# ad_1.net
KiCad netlist of a schematic drawn in Altium Designer
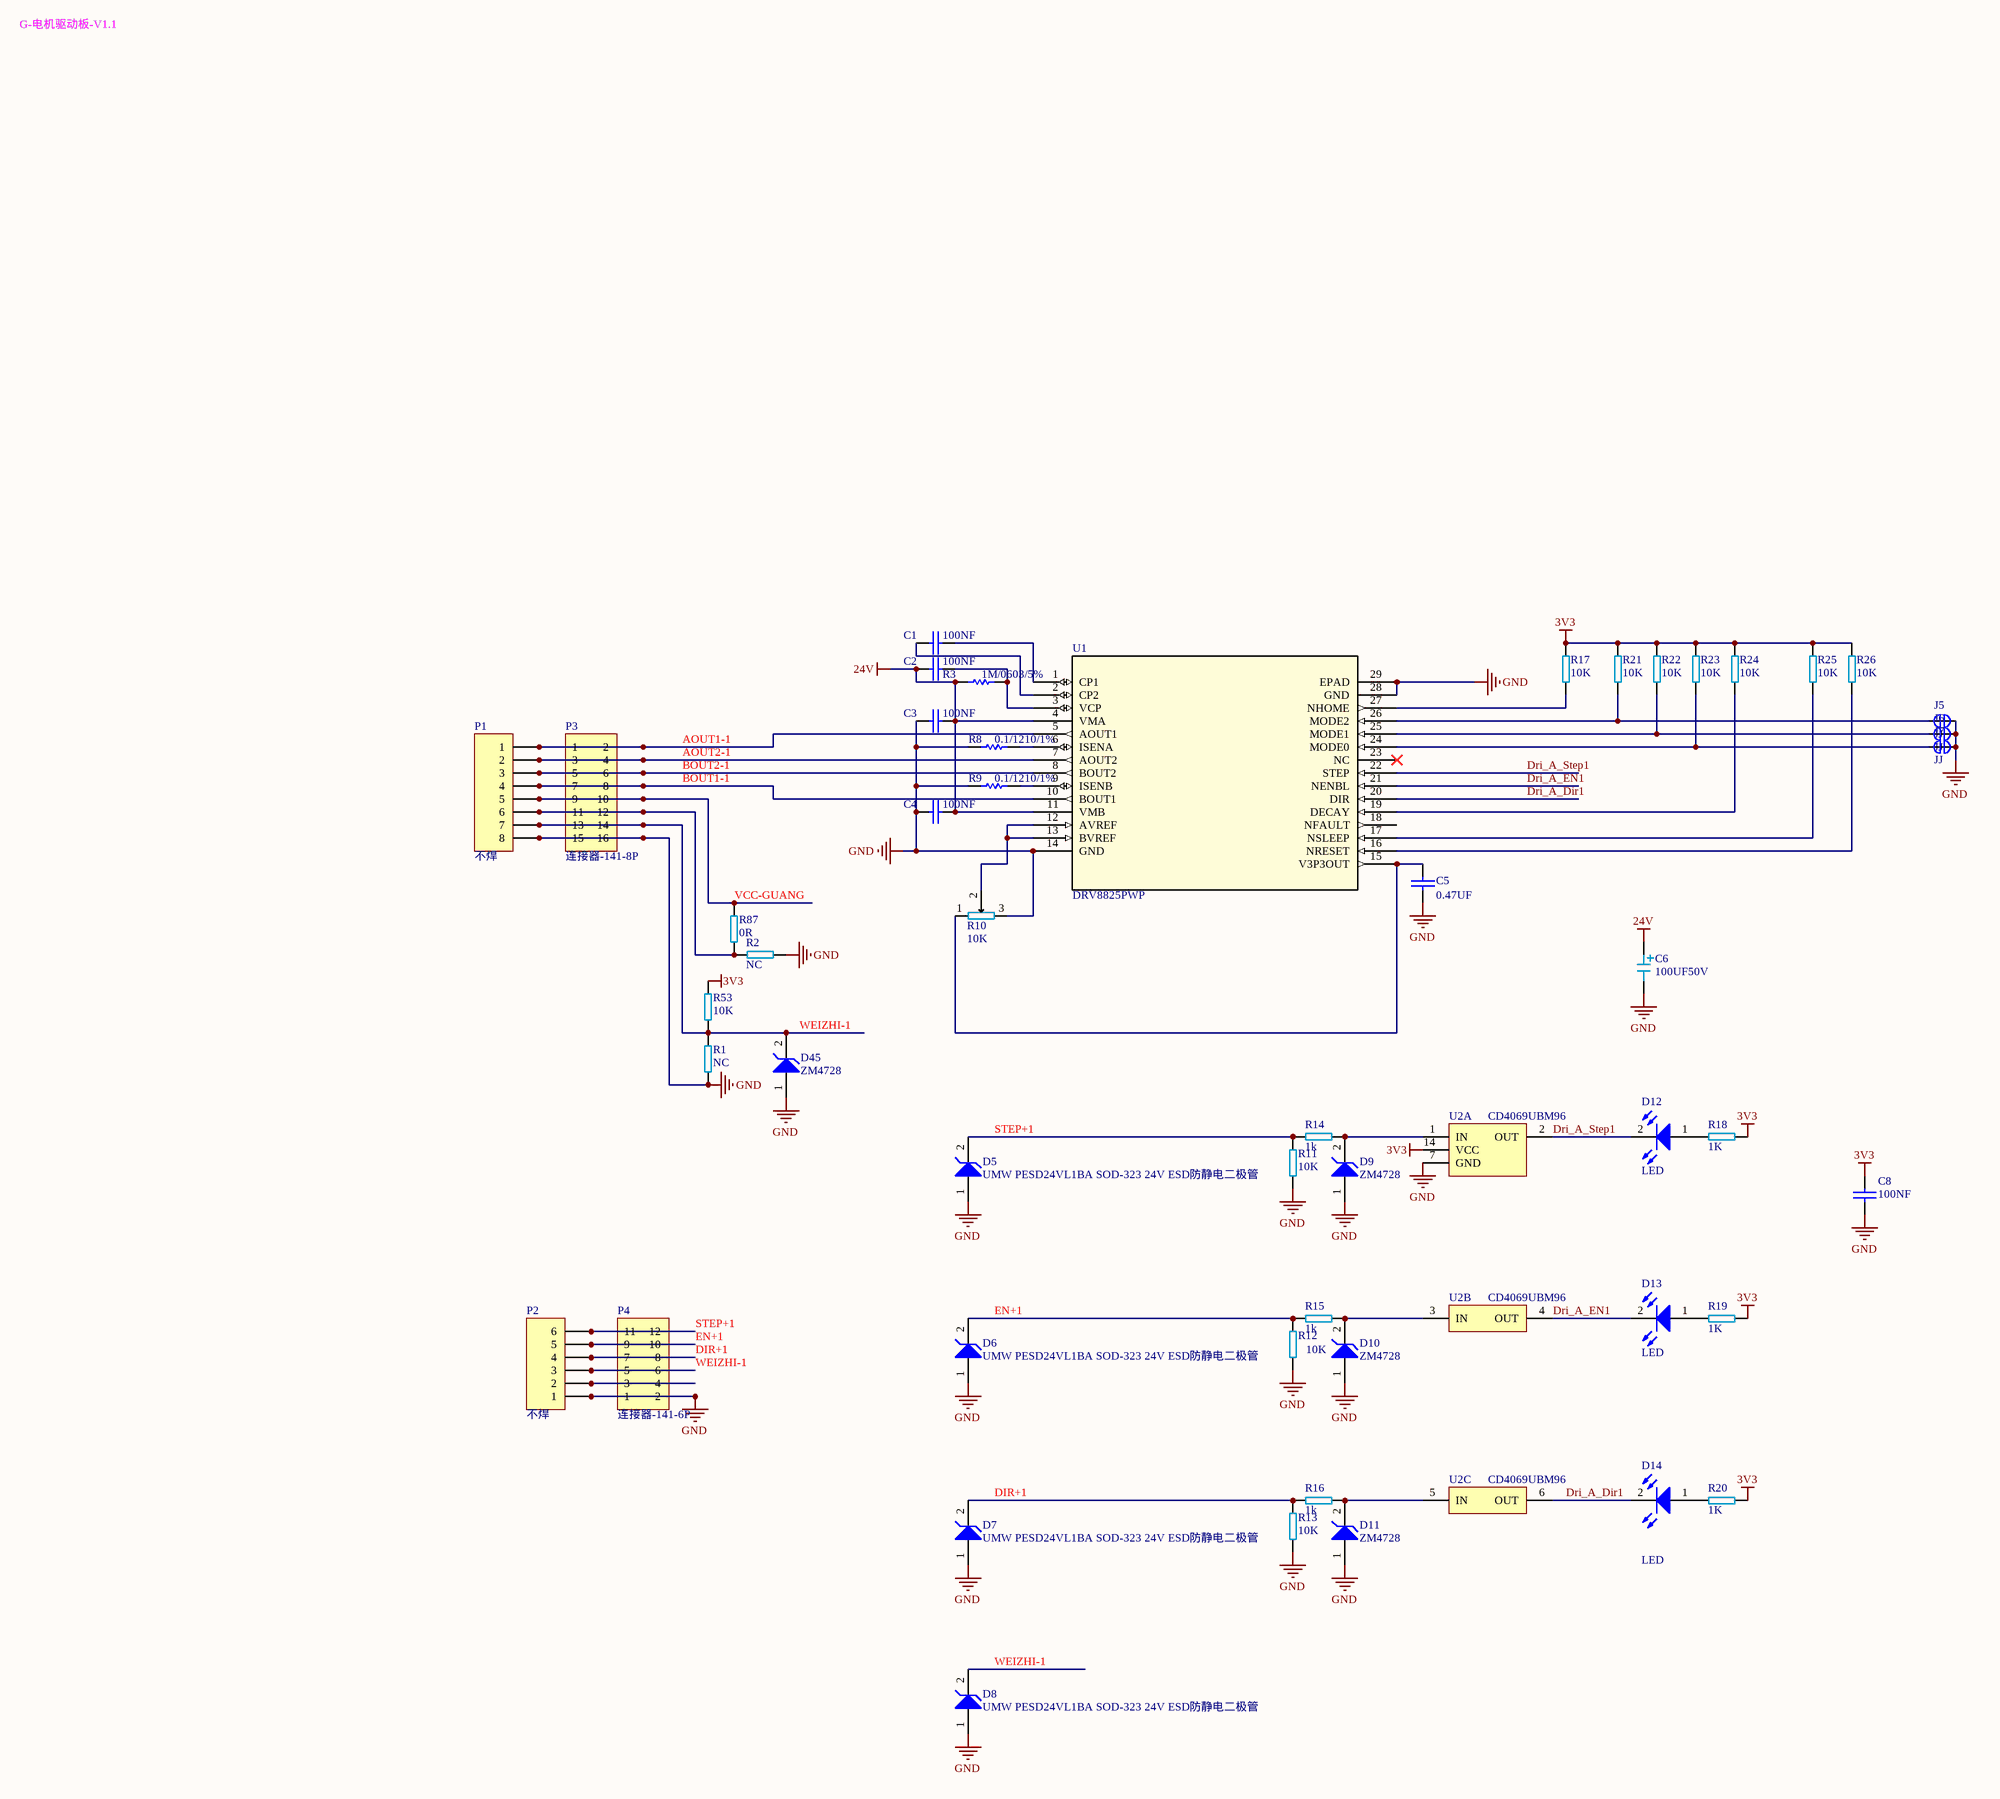
[diagram p0: ad_1.schdoc]

(export (version "E")
  (design (tool "Eeschema 10.0.6"))
  (components
    (comp (ref "C1")
      (value "100NF")
      (footprint "C0603")
      (description "Capacitor")
      (libsource (lib "Miscellaneous Devices") (part "CAP"))
    )
    (comp (ref "C2")
      (value "100NF")
      (footprint "C0603")
      (description "Capacitor")
      (libsource (lib "Miscellaneous Devices") (part "CAP"))
    )
    (comp (ref "C3")
      (value "100NF")
      (footprint "C0603")
      (description "Capacitor")
      (libsource (lib "Miscellaneous Devices") (part "CAP"))
    )
    (comp (ref "C4")
      (value "100NF")
      (footprint "C0603")
      (description "Capacitor")
      (libsource (lib "Miscellaneous Devices") (part "CAP"))
    )
    (comp (ref "C5")
      (value "0.47UF")
      (footprint "C0603")
      (description "Capacitor")
      (libsource (lib "Miscellaneous Devices") (part "CAP"))
    )
    (comp (ref "C6")
      (value "100UF50V")
      (footprint "CE8")
      (description "铝电解电容")
      (libsource (lib "base") (part "C+"))
    )
    (comp (ref "C8")
      (value "100NF")
      (footprint "C0603")
      (description "Capacitor")
      (libsource (lib "Miscellaneous Devices") (part "CAP"))
    )
    (comp (ref "D5")
      (value "UMW PESD24VL1BA SOD-323 24V ESD防静电二极管")
      (footprint "SOD323")
      (description "稳压管")
      (fields (field (name "PUBLISHER") "Altium Limited"))
      (libsource (lib "base") (part "TVS-SMA"))
    )
    (comp (ref "D6")
      (value "UMW PESD24VL1BA SOD-323 24V ESD防静电二极管")
      (footprint "SOD323")
      (description "稳压管")
      (fields (field (name "PUBLISHER") "Altium Limited"))
      (libsource (lib "base") (part "TVS-SMA"))
    )
    (comp (ref "D7")
      (value "UMW PESD24VL1BA SOD-323 24V ESD防静电二极管")
      (footprint "SOD323")
      (description "稳压管")
      (fields (field (name "PUBLISHER") "Altium Limited"))
      (libsource (lib "base") (part "TVS-SMA"))
    )
    (comp (ref "D8")
      (value "UMW PESD24VL1BA SOD-323 24V ESD防静电二极管")
      (footprint "SOD323")
      (description "稳压管")
      (fields (field (name "PUBLISHER") "Altium Limited"))
      (libsource (lib "base") (part "TVS-SMA"))
    )
    (comp (ref "D9")
      (value "ZM4728")
      (footprint "D1206")
      (description "稳压管")
      (fields (field (name "PUBLISHER") "Altium Limited"))
      (libsource (lib "base") (part "TVS-SMA"))
    )
    (comp (ref "D10")
      (value "ZM4728")
      (footprint "D1206")
      (description "稳压管")
      (fields (field (name "PUBLISHER") "Altium Limited"))
      (libsource (lib "base") (part "TVS-SMA"))
    )
    (comp (ref "D11")
      (value "ZM4728")
      (footprint "D1206")
      (description "稳压管")
      (fields (field (name "PUBLISHER") "Altium Limited"))
      (libsource (lib "base") (part "TVS-SMA"))
    )
    (comp (ref "D12")
      (value "LED")
      (footprint "LED0603")
      (description "LED0603")
      (fields (field (name "PUBLISHER") "Altium Limited"))
      (libsource (lib "base") (part "LED0603"))
    )
    (comp (ref "D13")
      (value "LED")
      (footprint "LED0603")
      (description "LED0603")
      (fields (field (name "PUBLISHER") "Altium Limited"))
      (libsource (lib "base") (part "LED0603"))
    )
    (comp (ref "D14")
      (value "LED")
      (footprint "LED0603")
      (description "LED0603")
      (fields (field (name "PUBLISHER") "Altium Limited"))
      (libsource (lib "base") (part "LED0603"))
    )
    (comp (ref "D45")
      (value "ZM4728")
      (footprint "D1206")
      (description "稳压管")
      (fields (field (name "PUBLISHER") "Altium Limited"))
      (libsource (lib "base") (part "TVS-SMA"))
    )
    (comp (ref "J5")
      (value "JJ")
      (footprint "TIAOXIAN-PAN")
      (description "跳线")
      (libsource (lib "base") (part "JJ"))
    )
    (comp (ref "J6")
      (value "JJ")
      (footprint "TIAOXIAN-PAN")
      (description "跳线")
      (libsource (lib "base") (part "JJ"))
    )
    (comp (ref "J7")
      (value "JJ")
      (footprint "TIAOXIAN-PAN")
      (description "跳线")
      (libsource (lib "base") (part "JJ"))
    )
    (comp (ref "P1")
      (value "不焊")
      (footprint "SIP8")
      (description "连接器")
      (fields (field (name "PUBLISHER") "Altium Limited"))
      (libsource (lib "base") (part "SIP8"))
    )
    (comp (ref "P2")
      (value "不焊")
      (footprint "SIP6")
      (description "连接器")
      (fields (field (name "PUBLISHER") "Altium Limited"))
      (libsource (lib "base") (part "SIP6"))
    )
    (comp (ref "P3")
      (value "连接器-141-8P")
      (footprint "141V-8P")
      (description "连接器")
      (fields (field (name "PUBLISHER") "Altium Limited"))
      (libsource (lib "base") (part "DIC16"))
    )
    (comp (ref "P4")
      (value "连接器-141-6P")
      (footprint "141V-6P")
      (description "连接器")
      (fields (field (name "PUBLISHER") "Altium Limited"))
      (libsource (lib "base") (part "DIC12"))
    )
    (comp (ref "R1")
      (value "NC")
      (footprint "R0603")
      (description "贴片电阻")
      (libsource (lib "base") (part "R-0603"))
    )
    (comp (ref "R2")
      (value "NC")
      (footprint "R0603")
      (description "贴片电阻")
      (libsource (lib "base") (part "R-0603"))
    )
    (comp (ref "R3")
      (value "1M/0603/5%")
      (footprint "R0603")
      (description "Resistor")
      (fields (field (name "PUBLISHER") "Altium Limited"))
      (libsource (lib "Miscellaneous Devices") (part "Res1"))
    )
    (comp (ref "R8")
      (value "0.1/1210/1%")
      (footprint "R1210")
      (description "Resistor")
      (fields (field (name "PUBLISHER") "Altium Limited"))
      (libsource (lib "Miscellaneous Devices") (part "Res1"))
    )
    (comp (ref "R9")
      (value "0.1/1210/1%")
      (footprint "R1210")
      (description "Resistor")
      (fields (field (name "PUBLISHER") "Altium Limited"))
      (libsource (lib "Miscellaneous Devices") (part "Res1"))
    )
    (comp (ref "R10")
      (value "10K")
      (footprint "RR-MINI-SMD")
      (description "电位器")
      (libsource (lib "base") (part "RR"))
    )
    (comp (ref "R11")
      (value "10K")
      (footprint "R0603")
      (description "贴片电阻")
      (libsource (lib "base") (part "R-0603"))
    )
    (comp (ref "R12")
      (value "10K")
      (footprint "R0603")
      (description "贴片电阻")
      (libsource (lib "base") (part "R-0603"))
    )
    (comp (ref "R13")
      (value "10K")
      (footprint "R0603")
      (description "贴片电阻")
      (libsource (lib "base") (part "R-0603"))
    )
    (comp (ref "R14")
      (value "1k")
      (footprint "R0603")
      (description "贴片电阻")
      (libsource (lib "base") (part "R-0603"))
    )
    (comp (ref "R15")
      (value "1k")
      (footprint "R0603")
      (description "贴片电阻")
      (libsource (lib "base") (part "R-0603"))
    )
    (comp (ref "R16")
      (value "1k")
      (footprint "R0603")
      (description "贴片电阻")
      (libsource (lib "base") (part "R-0603"))
    )
    (comp (ref "R17")
      (value "10K")
      (footprint "R0603")
      (description "贴片电阻")
      (libsource (lib "base") (part "R-0603"))
    )
    (comp (ref "R18")
      (value "1K")
      (footprint "R0603")
      (description "贴片电阻")
      (libsource (lib "base") (part "R-0603"))
    )
    (comp (ref "R19")
      (value "1K")
      (footprint "R0603")
      (description "贴片电阻")
      (libsource (lib "base") (part "R-0603"))
    )
    (comp (ref "R20")
      (value "1K")
      (footprint "R0603")
      (description "贴片电阻")
      (libsource (lib "base") (part "R-0603"))
    )
    (comp (ref "R21")
      (value "10K")
      (footprint "R0603")
      (description "贴片电阻")
      (libsource (lib "base") (part "R-0603"))
    )
    (comp (ref "R22")
      (value "10K")
      (footprint "R0603")
      (description "贴片电阻")
      (libsource (lib "base") (part "R-0603"))
    )
    (comp (ref "R23")
      (value "10K")
      (footprint "R0603")
      (description "贴片电阻")
      (libsource (lib "base") (part "R-0603"))
    )
    (comp (ref "R24")
      (value "10K")
      (footprint "R0603")
      (description "贴片电阻")
      (libsource (lib "base") (part "R-0603"))
    )
    (comp (ref "R25")
      (value "10K")
      (footprint "R0603")
      (description "贴片电阻")
      (libsource (lib "base") (part "R-0603"))
    )
    (comp (ref "R26")
      (value "10K")
      (footprint "R0603")
      (description "贴片电阻")
      (libsource (lib "base") (part "R-0603"))
    )
    (comp (ref "R53")
      (value "10K")
      (footprint "R0603")
      (description "贴片电阻")
      (libsource (lib "base") (part "R-0603"))
    )
    (comp (ref "R87")
      (value "0R")
      (footprint "R0603")
      (description "贴片电阻")
      (libsource (lib "base") (part "R-0603"))
    )
    (comp (ref "U1")
      (value "DRV8825PWP")
      (footprint "HTSSOP28")
      (description "芯片")
      (libsource (lib "User") (part "DRV8825PWP"))
    )
    (comp (ref "U2")
      (value "CD4069UBM96")
      (footprint "SO14")
      (description "芯片")
      (libsource (lib "Chip") (part "CD4069"))
    )
  )
  (nets
    (net (code "1") (name "/AOUT1-1") (class "Default")
      (node (ref "P1") (pin "1") (pinfunction "1_1") (pintype "passive"))
      (node (ref "P3") (pin "1") (pinfunction "1_1") (pintype "passive"))
      (node (ref "P3") (pin "2") (pinfunction "2_2") (pintype "passive"))
      (node (ref "U1") (pin "5") (pinfunction "AOUT1_5") (pintype "output"))
    )
    (net (code "2") (name "/AOUT2-1") (class "Default")
      (node (ref "P1") (pin "2") (pinfunction "2_2") (pintype "passive"))
      (node (ref "P3") (pin "3") (pinfunction "3_3") (pintype "passive"))
      (node (ref "P3") (pin "4") (pinfunction "4_4") (pintype "passive"))
      (node (ref "U1") (pin "7") (pinfunction "AOUT2_7") (pintype "output"))
    )
    (net (code "3") (name "/BOUT1-1") (class "Default")
      (node (ref "P1") (pin "4") (pinfunction "4_4") (pintype "passive"))
      (node (ref "P3") (pin "7") (pinfunction "7_7") (pintype "passive"))
      (node (ref "P3") (pin "8") (pinfunction "8_8") (pintype "passive"))
      (node (ref "U1") (pin "10") (pinfunction "BOUT1_10") (pintype "output"))
    )
    (net (code "4") (name "/BOUT2-1") (class "Default")
      (node (ref "P1") (pin "3") (pinfunction "3_3") (pintype "passive"))
      (node (ref "P3") (pin "5") (pinfunction "5_5") (pintype "passive"))
      (node (ref "P3") (pin "6") (pinfunction "6_6") (pintype "passive"))
      (node (ref "U1") (pin "8") (pinfunction "BOUT2_8") (pintype "output"))
    )
    (net (code "5") (name "/DIR+1") (class "Default")
      (node (ref "D7") (pin "2") (pinfunction "2_2") (pintype "passive"))
      (node (ref "P2") (pin "4") (pinfunction "4_4") (pintype "passive"))
      (node (ref "P4") (pin "7") (pinfunction "7_7") (pintype "passive"))
      (node (ref "P4") (pin "8") (pinfunction "8_8") (pintype "passive"))
      (node (ref "R13") (pin "2") (pinfunction "2_2") (pintype "passive"))
      (node (ref "R16") (pin "2") (pinfunction "2_2") (pintype "passive"))
    )
    (net (code "6") (name "/Dri_A_Dir1") (class "Default")
      (node (ref "D14") (pin "2") (pinfunction "K_2") (pintype "passive"))
      (node (ref "U1") (pin "20") (pinfunction "DIR_20") (pintype "input"))
      (node (ref "U2") (pin "6") (pinfunction "OUT_6") (pintype "passive"))
    )
    (net (code "7") (name "/Dri_A_EN1") (class "Default")
      (node (ref "D13") (pin "2") (pinfunction "K_2") (pintype "passive"))
      (node (ref "U1") (pin "21") (pinfunction "NENBL_21") (pintype "input"))
      (node (ref "U2") (pin "4") (pinfunction "OUT_4") (pintype "passive"))
    )
    (net (code "8") (name "/Dri_A_Step1") (class "Default")
      (node (ref "D12") (pin "2") (pinfunction "K_2") (pintype "passive"))
      (node (ref "U1") (pin "22") (pinfunction "STEP_22") (pintype "input"))
      (node (ref "U2") (pin "2") (pinfunction "OUT_2") (pintype "passive"))
    )
    (net (code "9") (name "/EN+1") (class "Default")
      (node (ref "D6") (pin "2") (pinfunction "2_2") (pintype "passive"))
      (node (ref "P2") (pin "5") (pinfunction "5_5") (pintype "passive"))
      (node (ref "P4") (pin "10") (pinfunction "10_10") (pintype "passive"))
      (node (ref "P4") (pin "9") (pinfunction "9_9") (pintype "passive"))
      (node (ref "R12") (pin "2") (pinfunction "2_2") (pintype "passive"))
      (node (ref "R15") (pin "2") (pinfunction "2_2") (pintype "passive"))
    )
    (net (code "11") (name "/STEP+1") (class "Default")
      (node (ref "D5") (pin "2") (pinfunction "2_2") (pintype "passive"))
      (node (ref "P2") (pin "6") (pinfunction "6_6") (pintype "passive"))
      (node (ref "P4") (pin "11") (pinfunction "11_11") (pintype "passive"))
      (node (ref "P4") (pin "12") (pinfunction "12_12") (pintype "passive"))
      (node (ref "R11") (pin "2") (pinfunction "2_2") (pintype "passive"))
      (node (ref "R14") (pin "2") (pinfunction "2_2") (pintype "passive"))
    )
    (net (code "12") (name "/VCC-GUANG") (class "Default")
      (node (ref "P1") (pin "5") (pinfunction "5_5") (pintype "passive"))
      (node (ref "P3") (pin "10") (pinfunction "10_10") (pintype "passive"))
      (node (ref "P3") (pin "9") (pinfunction "9_9") (pintype "passive"))
      (node (ref "R87") (pin "2") (pinfunction "2_2") (pintype "passive"))
    )
    (net (code "13") (name "/WEIZHI-1") (class "Default")
      (node (ref "D45") (pin "2") (pinfunction "2_2") (pintype "passive"))
      (node (ref "D8") (pin "2") (pinfunction "2_2") (pintype "passive"))
      (node (ref "P1") (pin "7") (pinfunction "7_7") (pintype "passive"))
      (node (ref "P2") (pin "3") (pinfunction "3_3") (pintype "passive"))
      (node (ref "P3") (pin "13") (pinfunction "13_13") (pintype "passive"))
      (node (ref "P3") (pin "14") (pinfunction "14_14") (pintype "passive"))
      (node (ref "P4") (pin "5") (pinfunction "5_5") (pintype "passive"))
      (node (ref "P4") (pin "6") (pinfunction "6_6") (pintype "passive"))
      (node (ref "R1") (pin "2") (pinfunction "2_2") (pintype "passive"))
      (node (ref "R53") (pin "1") (pinfunction "1_1") (pintype "passive"))
    )
    (net (code "14") (name "3V3") (class "Default")
      (node (ref "C8") (pin "2") (pinfunction "2_2") (pintype "passive"))
      (node (ref "R17") (pin "2") (pinfunction "2_2") (pintype "passive"))
      (node (ref "R18") (pin "2") (pinfunction "2_2") (pintype "passive"))
      (node (ref "R19") (pin "2") (pinfunction "2_2") (pintype "passive"))
      (node (ref "R20") (pin "2") (pinfunction "2_2") (pintype "passive"))
      (node (ref "R21") (pin "2") (pinfunction "2_2") (pintype "passive"))
      (node (ref "R22") (pin "2") (pinfunction "2_2") (pintype "passive"))
      (node (ref "R23") (pin "2") (pinfunction "2_2") (pintype "passive"))
      (node (ref "R24") (pin "2") (pinfunction "2_2") (pintype "passive"))
      (node (ref "R25") (pin "2") (pinfunction "2_2") (pintype "passive"))
      (node (ref "R26") (pin "2") (pinfunction "2_2") (pintype "passive"))
      (node (ref "R53") (pin "2") (pinfunction "2_2") (pintype "passive"))
      (node (ref "U2") (pin "14") (pinfunction "VCC_14") (pintype "passive"))
    )
    (net (code "15") (name "24V") (class "Default")
      (node (ref "C2") (pin "1") (pinfunction "1_1") (pintype "passive"))
      (node (ref "C3") (pin "2") (pinfunction "2_2") (pintype "passive"))
      (node (ref "C4") (pin "2") (pinfunction "2_2") (pintype "passive"))
      (node (ref "C6") (pin "1") (pinfunction "1_1") (pintype "passive"))
      (node (ref "R3") (pin "2") (pinfunction "2_2") (pintype "passive"))
      (node (ref "U1") (pin "11") (pinfunction "VMB_11") (pintype "power_in"))
      (node (ref "U1") (pin "4") (pinfunction "VMA_4") (pintype "power_in"))
    )
    (net (code "16") (name "GND") (class "Default")
      (node (ref "C3") (pin "1") (pinfunction "1_1") (pintype "passive"))
      (node (ref "C4") (pin "1") (pinfunction "1_1") (pintype "passive"))
      (node (ref "C5") (pin "1") (pinfunction "1_1") (pintype "passive"))
      (node (ref "C6") (pin "2") (pinfunction "2_2") (pintype "passive"))
      (node (ref "C8") (pin "1") (pinfunction "1_1") (pintype "passive"))
      (node (ref "D10") (pin "1") (pinfunction "1_1") (pintype "passive"))
      (node (ref "D11") (pin "1") (pinfunction "1_1") (pintype "passive"))
      (node (ref "D45") (pin "1") (pinfunction "1_1") (pintype "passive"))
      (node (ref "D5") (pin "1") (pinfunction "1_1") (pintype "passive"))
      (node (ref "D6") (pin "1") (pinfunction "1_1") (pintype "passive"))
      (node (ref "D7") (pin "1") (pinfunction "1_1") (pintype "passive"))
      (node (ref "D8") (pin "1") (pinfunction "1_1") (pintype "passive"))
      (node (ref "D9") (pin "1") (pinfunction "1_1") (pintype "passive"))
      (node (ref "J5") (pin "2") (pinfunction "2_2") (pintype "passive"))
      (node (ref "J6") (pin "2") (pinfunction "2_2") (pintype "passive"))
      (node (ref "J7") (pin "2") (pinfunction "2_2") (pintype "passive"))
      (node (ref "P1") (pin "8") (pinfunction "8_8") (pintype "passive"))
      (node (ref "P2") (pin "1") (pinfunction "1_1") (pintype "passive"))
      (node (ref "P3") (pin "15") (pinfunction "15_15") (pintype "passive"))
      (node (ref "P3") (pin "16") (pinfunction "16_16") (pintype "passive"))
      (node (ref "P4") (pin "1") (pinfunction "1_1") (pintype "passive"))
      (node (ref "P4") (pin "2") (pinfunction "2_2") (pintype "passive"))
      (node (ref "R1") (pin "1") (pinfunction "1_1") (pintype "passive"))
      (node (ref "R10") (pin "3") (pinfunction "3_3") (pintype "passive"))
      (node (ref "R11") (pin "1") (pinfunction "1_1") (pintype "passive"))
      (node (ref "R12") (pin "1") (pinfunction "1_1") (pintype "passive"))
      (node (ref "R13") (pin "1") (pinfunction "1_1") (pintype "passive"))
      (node (ref "R2") (pin "1") (pinfunction "1_1") (pintype "passive"))
      (node (ref "R8") (pin "2") (pinfunction "2_2") (pintype "passive"))
      (node (ref "R9") (pin "2") (pinfunction "2_2") (pintype "passive"))
      (node (ref "U1") (pin "14") (pinfunction "GND_14") (pintype "power_in"))
      (node (ref "U1") (pin "28") (pinfunction "GND_28") (pintype "power_in"))
      (node (ref "U1") (pin "29") (pinfunction "EPAD_29") (pintype "passive"))
      (node (ref "U2") (pin "7") (pinfunction "GND_7") (pintype "passive"))
    )
    (net (code "17") (name "Net-(D12-A)") (class "Default")
      (node (ref "D12") (pin "1") (pinfunction "A_1") (pintype "passive"))
      (node (ref "R18") (pin "1") (pinfunction "1_1") (pintype "passive"))
    )
    (net (code "18") (name "Net-(D13-A)") (class "Default")
      (node (ref "D13") (pin "1") (pinfunction "A_1") (pintype "passive"))
      (node (ref "R19") (pin "1") (pinfunction "1_1") (pintype "passive"))
    )
    (net (code "19") (name "Net-(D14-A)") (class "Default")
      (node (ref "D14") (pin "1") (pinfunction "A_1") (pintype "passive"))
      (node (ref "R20") (pin "1") (pinfunction "1_1") (pintype "passive"))
    )
    (net (code "20") (name "Net-(P1-Pad6)") (class "Default")
      (node (ref "P1") (pin "6") (pinfunction "6_6") (pintype "passive"))
      (node (ref "P3") (pin "11") (pinfunction "11_11") (pintype "passive"))
      (node (ref "P3") (pin "12") (pinfunction "12_12") (pintype "passive"))
      (node (ref "R2") (pin "2") (pinfunction "2_2") (pintype "passive"))
      (node (ref "R87") (pin "1") (pinfunction "1_1") (pintype "passive"))
    )
    (net (code "21") (name "Net-(P2-Pad2)") (class "Default")
      (node (ref "P2") (pin "2") (pinfunction "2_2") (pintype "passive"))
      (node (ref "P4") (pin "3") (pinfunction "3_3") (pintype "passive"))
      (node (ref "P4") (pin "4") (pinfunction "4_4") (pintype "passive"))
    )
    (net (code "22") (name "Net-(U1-AVREF)") (class "Default")
      (node (ref "R10") (pin "2") (pinfunction "2_2") (pintype "passive"))
      (node (ref "U1") (pin "12") (pinfunction "AVREF_12") (pintype "input"))
      (node (ref "U1") (pin "13") (pinfunction "BVREF_13") (pintype "input"))
    )
    (net (code "23") (name "Net-(U1-CP1)") (class "Default")
      (node (ref "C1") (pin "2") (pinfunction "2_2") (pintype "passive"))
      (node (ref "U1") (pin "1") (pinfunction "CP1_1") (pintype "bidirectional"))
    )
    (net (code "24") (name "Net-(U1-CP2)") (class "Default")
      (node (ref "C1") (pin "1") (pinfunction "1_1") (pintype "passive"))
      (node (ref "U1") (pin "2") (pinfunction "CP2_2") (pintype "bidirectional"))
    )
    (net (code "25") (name "Net-(U1-DECAY)") (class "Default")
      (node (ref "R24") (pin "1") (pinfunction "1_1") (pintype "passive"))
      (node (ref "U1") (pin "19") (pinfunction "DECAY_19") (pintype "input"))
    )
    (net (code "26") (name "Net-(U1-ISENA)") (class "Default")
      (node (ref "R8") (pin "1") (pinfunction "1_1") (pintype "passive"))
      (node (ref "U1") (pin "6") (pinfunction "ISENA_6") (pintype "bidirectional"))
    )
    (net (code "27") (name "Net-(U1-ISENB)") (class "Default")
      (node (ref "R9") (pin "1") (pinfunction "1_1") (pintype "passive"))
      (node (ref "U1") (pin "9") (pinfunction "ISENB_9") (pintype "bidirectional"))
    )
    (net (code "28") (name "Net-(U1-MODE0)") (class "Default")
      (node (ref "J7") (pin "1") (pinfunction "1_1") (pintype "passive"))
      (node (ref "R23") (pin "1") (pinfunction "1_1") (pintype "passive"))
      (node (ref "U1") (pin "24") (pinfunction "MODE0_24") (pintype "input"))
    )
    (net (code "29") (name "Net-(U1-MODE1)") (class "Default")
      (node (ref "J6") (pin "1") (pinfunction "1_1") (pintype "passive"))
      (node (ref "R22") (pin "1") (pinfunction "1_1") (pintype "passive"))
      (node (ref "U1") (pin "25") (pinfunction "MODE1_25") (pintype "input"))
    )
    (net (code "30") (name "Net-(U1-MODE2)") (class "Default")
      (node (ref "J5") (pin "1") (pinfunction "1_1") (pintype "passive"))
      (node (ref "R21") (pin "1") (pinfunction "1_1") (pintype "passive"))
      (node (ref "U1") (pin "26") (pinfunction "MODE2_26") (pintype "input"))
    )
    (net (code "31") (name "Net-(U1-NHOME)") (class "Default")
      (node (ref "R17") (pin "1") (pinfunction "1_1") (pintype "passive"))
      (node (ref "U1") (pin "27") (pinfunction "NHOME_27") (pintype "output"))
    )
    (net (code "32") (name "Net-(U1-NRESET)") (class "Default")
      (node (ref "R26") (pin "1") (pinfunction "1_1") (pintype "passive"))
      (node (ref "U1") (pin "16") (pinfunction "NRESET_16") (pintype "input"))
    )
    (net (code "33") (name "Net-(U1-NSLEEP)") (class "Default")
      (node (ref "R25") (pin "1") (pinfunction "1_1") (pintype "passive"))
      (node (ref "U1") (pin "17") (pinfunction "NSLEEP_17") (pintype "input"))
    )
    (net (code "34") (name "Net-(U1-V3P3OUT)") (class "Default")
      (node (ref "C5") (pin "2") (pinfunction "2_2") (pintype "passive"))
      (node (ref "R10") (pin "1") (pinfunction "1_1") (pintype "passive"))
      (node (ref "U1") (pin "15") (pinfunction "V3P3OUT_15") (pintype "output"))
    )
    (net (code "35") (name "Net-(U1-VCP)") (class "Default")
      (node (ref "C2") (pin "2") (pinfunction "2_2") (pintype "passive"))
      (node (ref "R3") (pin "1") (pinfunction "1_1") (pintype "passive"))
      (node (ref "U1") (pin "3") (pinfunction "VCP_3") (pintype "bidirectional"))
    )
    (net (code "36") (name "Net-(U2A-IN)") (class "Default")
      (node (ref "D9") (pin "2") (pinfunction "2_2") (pintype "passive"))
      (node (ref "R14") (pin "1") (pinfunction "1_1") (pintype "passive"))
      (node (ref "U2") (pin "1") (pinfunction "IN_1") (pintype "passive"))
    )
    (net (code "37") (name "Net-(U2B-IN)") (class "Default")
      (node (ref "D10") (pin "2") (pinfunction "2_2") (pintype "passive"))
      (node (ref "R15") (pin "1") (pinfunction "1_1") (pintype "passive"))
      (node (ref "U2") (pin "3") (pinfunction "IN_3") (pintype "passive"))
    )
    (net (code "38") (name "Net-(U2C-IN)") (class "Default")
      (node (ref "D11") (pin "2") (pinfunction "2_2") (pintype "passive"))
      (node (ref "R16") (pin "1") (pinfunction "1_1") (pintype "passive"))
      (node (ref "U2") (pin "5") (pinfunction "IN_5") (pintype "passive"))
    )
    (net (code "39") (name "unconnected-(U1-NC-Pad23)") (class "Default")
      (node (ref "U1") (pin "23") (pinfunction "NC_23") (pintype "passive+no_connect"))
    )
    (net (code "40") (name "unconnected-(U1-NFAULT-Pad18)") (class "Default")
      (node (ref "U1") (pin "18") (pinfunction "NFAULT_18") (pintype "output"))
    )
  )
)
